# Power.net
KiCad netlist of a schematic drawn in Altium Designer
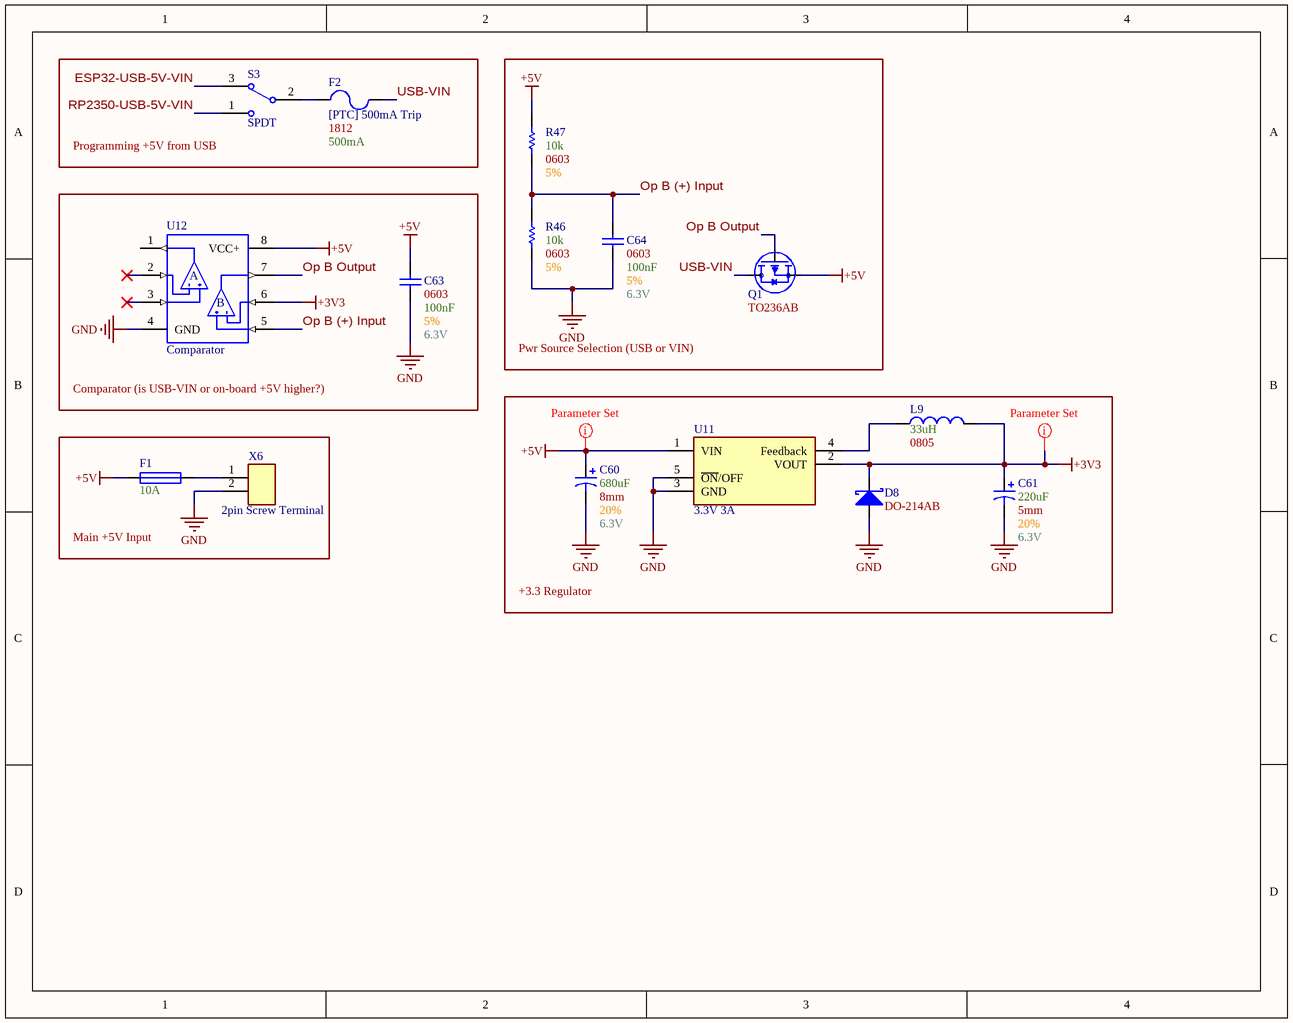
[diagram p0: Power.SchDoc]

(export (version "E")
  (design (tool "Eeschema 10.0.6"))
  (components
    (comp (ref "C60")
      (value "SMD Polarized")
      (footprint "[Cap] SMD Polarized, 8mm")
      (fields
        (field (name "TOLERANCE") "20%")
        (field (name "MAX VOLTAGE") "6.3V")
        (field (name "CAPACITANCE") "680uF")
        (field (name "DIAMETER") "8mm")
      )
      (libsource (lib "RADM Components") (part "[Cap] SMD Polarized"))
    )
    (comp (ref "C61")
      (value "SMD Polarized")
      (footprint "[Cap] SMD Polarized, 5mm")
      (fields
        (field (name "TOLERANCE") "20%")
        (field (name "MAX VOLTAGE") "6.3V")
        (field (name "CAPACITANCE") "220uF")
        (field (name "DIAMETER") "5mm")
      )
      (libsource (lib "RADM Components") (part "[Cap] SMD Polarized"))
    )
    (comp (ref "C63")
      (value "[Cap] SMD Nonpolarized")
      (footprint "[Cap] SMD 0603")
      (fields
        (field (name "SIZE PACKAGE") "0603")
        (field (name "CAPACITANCE") "100nF")
        (field (name "VOLTAGE") "6.3V")
        (field (name "TOLERANCE") "5%")
      )
      (libsource (lib "RADM Components") (part "[Cap] SMD Nonpolarized"))
    )
    (comp (ref "C64")
      (value "[Cap] SMD Nonpolarized")
      (footprint "[Cap] SMD 0603")
      (fields
        (field (name "SIZE PACKAGE") "0603")
        (field (name "CAPACITANCE") "100nF")
        (field (name "VOLTAGE") "6.3V")
        (field (name "TOLERANCE") "5%")
      )
      (libsource (lib "RADM Components") (part "[Cap] SMD Nonpolarized"))
    )
    (comp (ref "D8")
      (value "Schottky")
      (footprint "[Diode] SMD DO-214AB")
      (description "Generic")
      (fields (field (name "SIZE PACKAGE") "DO-214AB"))
      (libsource (lib "RADM Components") (part "[Diode] SMD Schottky"))
    )
    (comp (ref "F1")
      (value "Right-Angle")
      (footprint "[Fuse] Blade Right-Angle")
      (fields (field (name "AMPERAGE") "10A"))
      (libsource (lib "RADM Components") (part "[Fuse] Blade Right-Angle"))
    )
    (comp (ref "F2")
      (value "[PTC] 500mA Trip")
      (footprint "[PTC] 500mA Trip")
      (description "MF-MSMF050-2")
      (fields (field (name "SIZE PACKAGE") "1812") (field (name "TRIP CURRENT") "500mA"))
      (libsource (lib "RADM Components") (part "[PTC] 500mA Trip"))
    )
    (comp (ref "L9")
      (value "SMD Inductor")
      (footprint "[Inductor] SMD 0805")
      (fields (field (name "SIZE PACKAGE") "0805") (field (name "INDUCTANCE") "33uH"))
      (libsource (lib "RADM Components") (part "[Inductor] SMD Inductor"))
    )
    (comp (ref "Q1")
      (value "PMV48XP")
      (footprint "[FET] P-Channel Mosfet")
      (fields (field (name "SIZE PACKAGE") "TO236AB"))
      (libsource (lib "RADM Components") (part "[FET] P-Channel MOSFET"))
    )
    (comp (ref "R46")
      (value "[Res] SMD Resistor")
      (footprint "[Res] SMD 0603")
      (description "Generic")
      (fields
        (field (name "RESISTANCE") "10k")
        (field (name "SIZE PACKAGE") "0603")
        (field (name "TOLERANCE") "5%")
      )
      (libsource (lib "RADM Components") (part "[Res] SMD Resistor"))
    )
    (comp (ref "R47")
      (value "[Res] SMD Resistor")
      (footprint "[Res] SMD 0603")
      (description "Generic")
      (fields
        (field (name "RESISTANCE") "10k")
        (field (name "SIZE PACKAGE") "0603")
        (field (name "TOLERANCE") "5%")
      )
      (libsource (lib "RADM Components") (part "[Res] SMD Resistor"))
    )
    (comp (ref "S3")
      (value "SPDT")
      (footprint "[Switch] SPDT")
      (libsource (lib "RADM Components") (part "[Switch] SPDT Switch"))
    )
    (comp (ref "U11")
      (value "3.3V 3A")
      (footprint "[Reg] 3V3 Regulator (4)")
      (description "3A")
      (libsource (lib "RADM Components") (part "[Reg] 3V3 Regulator (4)"))
    )
    (comp (ref "U12")
      (value "Comparator")
      (footprint "[IC] Dual Op-Ap")
      (description "LMV358IDGKR")
      (libsource (lib "RADM Components") (part "[IC] Dual Op-Amp"))
    )
    (comp (ref "X6")
      (value "2pin Screw Terminal")
      (footprint "[Screw Terminal] 2pin 5mm")
      (libsource (lib "RADM Connectors") (part "[Screw Terminal] 2pin"))
    )
  )
  (nets
    (net (code "1") (name "+3V3") (class "Default")
      (node (ref "C61") (pin "1") (pinfunction "1_1") (pintype "passive"))
      (node (ref "D8") (pin "1") (pinfunction "K_1") (pintype "power_in"))
      (node (ref "L9") (pin "2") (pinfunction "2_2") (pintype "passive"))
      (node (ref "U11") (pin "2") (pinfunction "VOUT_2") (pintype "passive"))
      (node (ref "U12") (pin "6") (pinfunction "2IN-_6") (pintype "input"))
    )
    (net (code "2") (name "+5V") (class "Default")
      (node (ref "C60") (pin "1") (pinfunction "1_1") (pintype "passive"))
      (node (ref "C63") (pin "2") (pinfunction "2_2") (pintype "passive"))
      (node (ref "F1") (pin "1") (pinfunction "1_1") (pintype "passive"))
      (node (ref "Q1") (pin "2") (pinfunction "S_2") (pintype "passive"))
      (node (ref "R47") (pin "2") (pinfunction "2_2") (pintype "passive"))
      (node (ref "U11") (pin "1") (pinfunction "VIN_1") (pintype "passive"))
      (node (ref "U12") (pin "8") (pinfunction "VCC+_8") (pintype "power_in"))
    )
    (net (code "3") (name "/ESP32-USB-5V-VIN") (class "Default")
      (node (ref "S3") (pin "3") (pinfunction "3_3") (pintype "passive"))
    )
    (net (code "4") (name "/Op B (+) Input") (class "Default")
      (node (ref "C64") (pin "2") (pinfunction "2_2") (pintype "passive"))
      (node (ref "R46") (pin "2") (pinfunction "2_2") (pintype "passive"))
      (node (ref "R47") (pin "1") (pinfunction "1_1") (pintype "passive"))
      (node (ref "U12") (pin "5") (pinfunction "2IN+_5") (pintype "input"))
    )
    (net (code "5") (name "/Op B Output") (class "Default")
      (node (ref "Q1") (pin "1") (pinfunction "G_1") (pintype "passive"))
      (node (ref "U12") (pin "7") (pinfunction "2OUT_7") (pintype "output"))
    )
    (net (code "6") (name "/RP2350-USB-5V-VIN") (class "Default")
      (node (ref "S3") (pin "1") (pinfunction "1_1") (pintype "passive"))
    )
    (net (code "7") (name "/USB-VIN") (class "Default")
      (node (ref "F2") (pin "2") (pinfunction "2_2") (pintype "passive"))
      (node (ref "Q1") (pin "3") (pinfunction "D_3") (pintype "passive"))
    )
    (net (code "8") (name "GND") (class "Default")
      (node (ref "C60") (pin "2") (pinfunction "2_2") (pintype "passive"))
      (node (ref "C61") (pin "2") (pinfunction "2_2") (pintype "passive"))
      (node (ref "C63") (pin "1") (pinfunction "1_1") (pintype "passive"))
      (node (ref "C64") (pin "1") (pinfunction "1_1") (pintype "passive"))
      (node (ref "D8") (pin "2") (pinfunction "A_2") (pintype "power_in"))
      (node (ref "R46") (pin "1") (pinfunction "1_1") (pintype "passive"))
      (node (ref "U11") (pin "3") (pinfunction "GND_3") (pintype "passive"))
      (node (ref "U11") (pin "5") (pinfunction "~{ON}/OFF_5") (pintype "passive"))
      (node (ref "U12") (pin "4") (pinfunction "GND_4") (pintype "power_in"))
      (node (ref "X6") (pin "2") (pintype "power_in"))
    )
    (net (code "9") (name "Net-(F1-Pad2)") (class "Default")
      (node (ref "F1") (pin "2") (pinfunction "2_2") (pintype "passive"))
      (node (ref "X6") (pin "1") (pintype "power_in"))
    )
    (net (code "10") (name "Net-(F2-Pad1)") (class "Default")
      (node (ref "F2") (pin "1") (pinfunction "1_1") (pintype "passive"))
      (node (ref "S3") (pin "2") (pinfunction "2_2") (pintype "passive"))
    )
    (net (code "11") (name "Net-(U11-Feedback)") (class "Default")
      (node (ref "L9") (pin "1") (pinfunction "1_1") (pintype "passive"))
      (node (ref "U11") (pin "4") (pinfunction "Feedback_4") (pintype "passive"))
    )
    (net (code "12") (name "unconnected-(U12-1IN+-Pad3)") (class "Default")
      (node (ref "U12") (pin "3") (pinfunction "1IN+_3") (pintype "input+no_connect"))
    )
    (net (code "13") (name "unconnected-(U12-1IN--Pad2)") (class "Default")
      (node (ref "U12") (pin "2") (pinfunction "1IN-_2") (pintype "input+no_connect"))
    )
    (net (code "14") (name "unconnected-(U12-1OUT-Pad1)") (class "Default")
      (node (ref "U12") (pin "1") (pinfunction "1OUT_1") (pintype "output"))
    )
  )
)
